# barrel.net
KiCad netlist of a schematic drawn in EAGLE
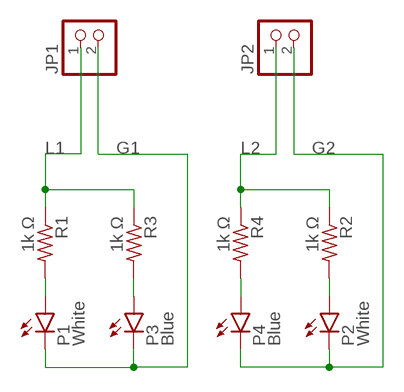
[diagram p0: schematic, sheet 1]

(export (version "E")
  (design (tool "Eeschema 10.0.6"))
  (components
    (comp (ref "JP1")
      (value "PINHD-1X2")
      (footprint "eagle-import:1X02")
      (libsource (lib "eagle-import") (part "PINHD-1X2"))
    )
    (comp (ref "JP2")
      (value "PINHD-1X2")
      (footprint "eagle-import:1X02")
      (libsource (lib "eagle-import") (part "PINHD-1X2"))
    )
    (comp (ref "P1")
      (value "White")
      (footprint "eagle-import:CHIP-LED0805")
      (libsource (lib "eagle-import") (part "LEDCHIP-LED0805"))
    )
    (comp (ref "P2")
      (value "White")
      (footprint "eagle-import:CHIP-LED0805")
      (libsource (lib "eagle-import") (part "LEDCHIP-LED0805"))
    )
    (comp (ref "P3")
      (value "Blue")
      (footprint "eagle-import:CHIP-LED0805")
      (libsource (lib "eagle-import") (part "LEDCHIP-LED0805"))
    )
    (comp (ref "P4")
      (value "Blue")
      (footprint "eagle-import:CHIP-LED0805")
      (libsource (lib "eagle-import") (part "LEDCHIP-LED0805"))
    )
    (comp (ref "R1")
      (value "1k Ω")
      (footprint "eagle-import:M0805")
      (libsource (lib "eagle-import") (part "R-US_M0805"))
    )
    (comp (ref "R2")
      (value "1k Ω")
      (footprint "eagle-import:M0805")
      (libsource (lib "eagle-import") (part "R-US_M0805"))
    )
    (comp (ref "R3")
      (value "1k Ω")
      (footprint "eagle-import:M0805")
      (libsource (lib "eagle-import") (part "R-US_M0805"))
    )
    (comp (ref "R4")
      (value "1k Ω")
      (footprint "eagle-import:M0805")
      (libsource (lib "eagle-import") (part "R-US_M0805"))
    )
  )
  (nets
    (net (code "1") (name "/G1") (class "Default")
      (node (ref "JP1") (pin "2") (pinfunction "2_2") (pintype "passive"))
      (node (ref "P1") (pin "C") (pinfunction "C_C") (pintype "passive"))
      (node (ref "P3") (pin "C") (pinfunction "C_C") (pintype "passive"))
    )
    (net (code "2") (name "/G2") (class "Default")
      (node (ref "JP2") (pin "2") (pinfunction "2_2") (pintype "passive"))
      (node (ref "P2") (pin "C") (pinfunction "C_C") (pintype "passive"))
      (node (ref "P4") (pin "C") (pinfunction "C_C") (pintype "passive"))
    )
    (net (code "3") (name "/L1") (class "Default")
      (node (ref "JP1") (pin "1") (pinfunction "1_1") (pintype "passive"))
      (node (ref "R1") (pin "1") (pinfunction "1_1") (pintype "passive"))
      (node (ref "R3") (pin "1") (pinfunction "1_1") (pintype "passive"))
    )
    (net (code "4") (name "/L2") (class "Default")
      (node (ref "JP2") (pin "1") (pinfunction "1_1") (pintype "passive"))
      (node (ref "R2") (pin "1") (pinfunction "1_1") (pintype "passive"))
      (node (ref "R4") (pin "1") (pinfunction "1_1") (pintype "passive"))
    )
    (net (code "5") (name "Net-(P1-PadA)") (class "Default")
      (node (ref "P1") (pin "A") (pinfunction "A_A") (pintype "passive"))
      (node (ref "R1") (pin "2") (pinfunction "2_2") (pintype "passive"))
    )
    (net (code "6") (name "Net-(P2-PadA)") (class "Default")
      (node (ref "P2") (pin "A") (pinfunction "A_A") (pintype "passive"))
      (node (ref "R2") (pin "2") (pinfunction "2_2") (pintype "passive"))
    )
    (net (code "7") (name "Net-(P3-PadA)") (class "Default")
      (node (ref "P3") (pin "A") (pinfunction "A_A") (pintype "passive"))
      (node (ref "R3") (pin "2") (pinfunction "2_2") (pintype "passive"))
    )
    (net (code "8") (name "Net-(P4-PadA)") (class "Default")
      (node (ref "P4") (pin "A") (pinfunction "A_A") (pintype "passive"))
      (node (ref "R4") (pin "2") (pinfunction "2_2") (pintype "passive"))
    )
  )
)
